# WL-FPGA.net
KiCad netlist of a schematic drawn in Altium Designer
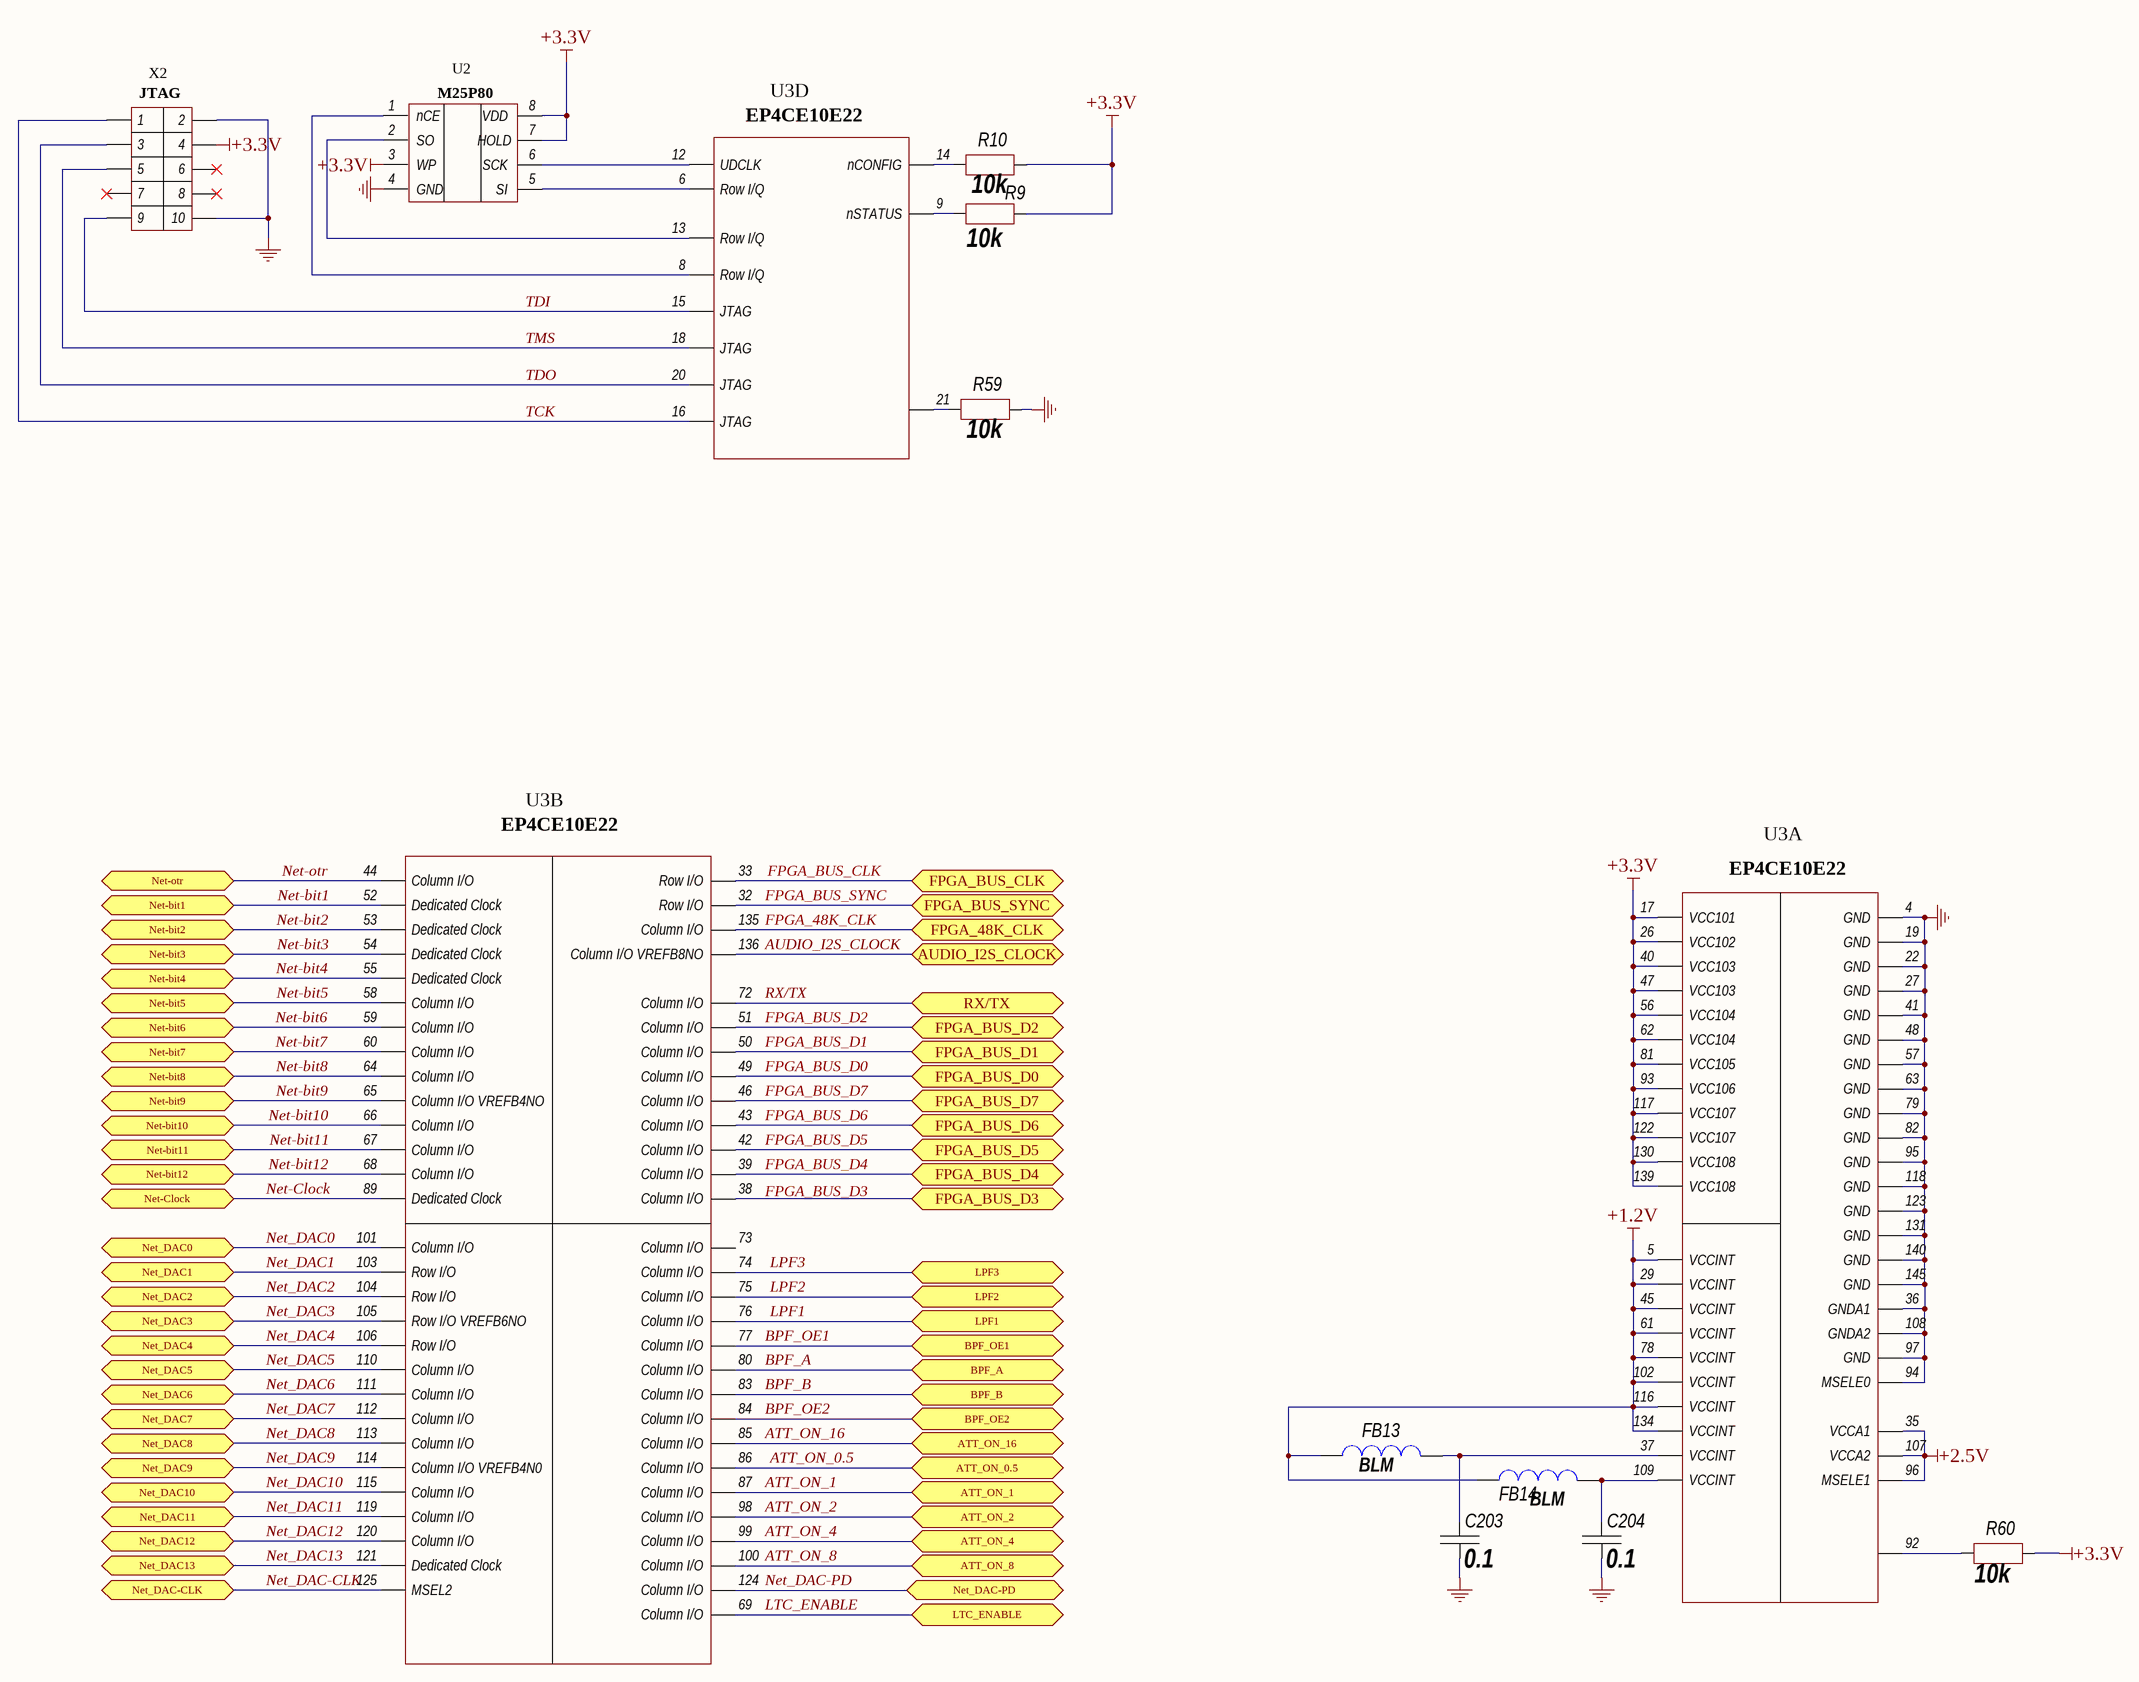
[diagram p0: WL-FPGA.SchDoc]

(export (version "E")
  (design (tool "Eeschema 10.0.6"))
  (components
    (comp (ref "C203")
      (value "0.1")
      (footprint "standard:CH0805C")
      (libsource (lib "Discrete") (part "Capacitor"))
    )
    (comp (ref "C204")
      (value "0.1")
      (footprint "standard:CH0805C")
      (libsource (lib "Discrete") (part "Capacitor"))
    )
    (comp (ref "FB13")
      (value "BLM")
      (footprint "standard:CH0805L")
      (libsource (lib "Discrete") (part "Inductor"))
    )
    (comp (ref "FB14")
      (value "BLM")
      (footprint "standard:CH0805L")
      (libsource (lib "Discrete") (part "Inductor"))
    )
    (comp (ref "R9")
      (value "10k")
      (footprint "standard:CH0805R")
      (libsource (lib "Discrete") (part "Resistor"))
    )
    (comp (ref "R10")
      (value "10k")
      (footprint "standard:CH0805R")
      (libsource (lib "Discrete") (part "Resistor"))
    )
    (comp (ref "R59")
      (value "10k")
      (footprint "standard:CH0805R")
      (libsource (lib "Discrete") (part "Resistor"))
    )
    (comp (ref "R60")
      (value "10k")
      (footprint "standard:CH0805R")
      (libsource (lib "Discrete") (part "Resistor"))
    )
    (comp (ref "U2") (value "M25P80") (footprint "8-SOIC") (libsource (lib "Digital") (part "M25P80")))
    (comp (ref "U3")
      (value "EP4CE10E22")
      (footprint "144-QFN")
      (libsource (lib "Digital") (part "EP4CE10E22C8N"))
    )
    (comp (ref "X2") (value "JTAG") (footprint "CON: PLD-10") (libsource (lib "Connectors") (part "Jtag")))
  )
  (nets
    (net (code "1") (name "+1.2V") (class "Default")
      (node (ref "FB13") (pin "2") (pinfunction "2_2") (pintype "passive"))
      (node (ref "FB14") (pin "2") (pinfunction "2_2") (pintype "passive"))
      (node (ref "U3") (pin "102") (pinfunction "VCCINT_102") (pintype "passive"))
      (node (ref "U3") (pin "116") (pinfunction "VCCINT_116") (pintype "passive"))
      (node (ref "U3") (pin "134") (pinfunction "VCCINT_134") (pintype "passive"))
      (node (ref "U3") (pin "29") (pinfunction "VCCINT_29") (pintype "passive"))
      (node (ref "U3") (pin "45") (pinfunction "VCCINT_45") (pintype "passive"))
      (node (ref "U3") (pin "5") (pinfunction "VCCINT_5") (pintype "passive"))
      (node (ref "U3") (pin "61") (pinfunction "VCCINT_61") (pintype "passive"))
      (node (ref "U3") (pin "78") (pinfunction "VCCINT_78") (pintype "passive"))
    )
    (net (code "2") (name "+2.5V") (class "Default")
      (node (ref "U3") (pin "107") (pinfunction "VCCA2_107") (pintype "passive"))
      (node (ref "U3") (pin "35") (pinfunction "VCCA1_35") (pintype "passive"))
      (node (ref "U3") (pin "96") (pinfunction "MSELE1_96") (pintype "passive"))
    )
    (net (code "3") (name "+3.3V") (class "Default")
      (node (ref "R10") (pin "1") (pinfunction "1_1") (pintype "passive"))
      (node (ref "R60") (pin "1") (pinfunction "1_1") (pintype "passive"))
      (node (ref "R9") (pin "1") (pinfunction "1_1") (pintype "passive"))
      (node (ref "U2") (pin "3") (pinfunction "WP_3") (pintype "passive"))
      (node (ref "U2") (pin "7") (pinfunction "HOLD_7") (pintype "passive"))
      (node (ref "U2") (pin "8") (pinfunction "VDD_8") (pintype "passive"))
      (node (ref "U3") (pin "117") (pinfunction "VCC107_117") (pintype "passive"))
      (node (ref "U3") (pin "122") (pinfunction "VCC107_122") (pintype "passive"))
      (node (ref "U3") (pin "130") (pinfunction "VCC108_130") (pintype "passive"))
      (node (ref "U3") (pin "139") (pinfunction "VCC108_139") (pintype "passive"))
      (node (ref "U3") (pin "17") (pinfunction "VCC101_17") (pintype "passive"))
      (node (ref "U3") (pin "26") (pinfunction "VCC102_26") (pintype "passive"))
      (node (ref "U3") (pin "40") (pinfunction "VCC103_40") (pintype "passive"))
      (node (ref "U3") (pin "47") (pinfunction "VCC103_47") (pintype "passive"))
      (node (ref "U3") (pin "56") (pinfunction "VCC104_56") (pintype "passive"))
      (node (ref "U3") (pin "62") (pinfunction "VCC104_62") (pintype "passive"))
      (node (ref "U3") (pin "81") (pinfunction "VCC105_81") (pintype "passive"))
      (node (ref "U3") (pin "93") (pinfunction "VCC106_93") (pintype "passive"))
      (node (ref "X2") (pin "4") (pinfunction "4_4") (pintype "power_in"))
    )
    (net (code "4") (name "/ATT_ON_0.5") (class "Default")
      (node (ref "U3") (pin "86") (pinfunction "Column_I/O_86") (pintype "passive"))
    )
    (net (code "5") (name "/ATT_ON_1") (class "Default")
      (node (ref "U3") (pin "87") (pinfunction "Column_I/O_87") (pintype "passive"))
    )
    (net (code "6") (name "/ATT_ON_2") (class "Default")
      (node (ref "U3") (pin "98") (pinfunction "Column_I/O_98") (pintype "passive"))
    )
    (net (code "7") (name "/ATT_ON_4") (class "Default")
      (node (ref "U3") (pin "99") (pinfunction "Column_I/O_99") (pintype "passive"))
    )
    (net (code "8") (name "/ATT_ON_8") (class "Default")
      (node (ref "U3") (pin "100") (pinfunction "Column_I/O_100") (pintype "passive"))
    )
    (net (code "9") (name "/ATT_ON_16") (class "Default")
      (node (ref "U3") (pin "85") (pinfunction "Column_I/O_85") (pintype "passive"))
    )
    (net (code "10") (name "/AUDIO_I2S_CLOCK") (class "Default")
      (node (ref "U3") (pin "136") (pinfunction "Column_I/O_VREFB8NO_136") (pintype "passive"))
    )
    (net (code "11") (name "/BPF_A") (class "Default")
      (node (ref "U3") (pin "80") (pinfunction "Column_I/O_80") (pintype "passive"))
    )
    (net (code "12") (name "/BPF_B") (class "Default")
      (node (ref "U3") (pin "83") (pinfunction "Column_I/O_83") (pintype "passive"))
    )
    (net (code "13") (name "/BPF_OE1") (class "Default")
      (node (ref "U3") (pin "77") (pinfunction "Column_I/O_77") (pintype "passive"))
    )
    (net (code "14") (name "/BPF_OE2") (class "Default")
      (node (ref "U3") (pin "84") (pinfunction "Column_I/O_84") (pintype "passive"))
    )
    (net (code "15") (name "/FPGA_48K_CLK") (class "Default")
      (node (ref "U3") (pin "135") (pinfunction "Column_I/O_135") (pintype "passive"))
    )
    (net (code "16") (name "/FPGA_BUS_CLK") (class "Default")
      (node (ref "U3") (pin "33") (pinfunction "Row_I/O_33") (pintype "passive"))
    )
    (net (code "17") (name "/FPGA_BUS_D0") (class "Default")
      (node (ref "U3") (pin "49") (pinfunction "Column_I/O_49") (pintype "passive"))
    )
    (net (code "18") (name "/FPGA_BUS_D1") (class "Default")
      (node (ref "U3") (pin "50") (pinfunction "Column_I/O_50") (pintype "passive"))
    )
    (net (code "19") (name "/FPGA_BUS_D2") (class "Default")
      (node (ref "U3") (pin "51") (pinfunction "Column_I/O_51") (pintype "passive"))
    )
    (net (code "20") (name "/FPGA_BUS_D3") (class "Default")
      (node (ref "U3") (pin "38") (pinfunction "Column_I/O_38") (pintype "passive"))
    )
    (net (code "21") (name "/FPGA_BUS_D4") (class "Default")
      (node (ref "U3") (pin "39") (pinfunction "Column_I/O_39") (pintype "passive"))
    )
    (net (code "22") (name "/FPGA_BUS_D5") (class "Default")
      (node (ref "U3") (pin "42") (pinfunction "Column_I/O_42") (pintype "passive"))
    )
    (net (code "23") (name "/FPGA_BUS_D6") (class "Default")
      (node (ref "U3") (pin "43") (pinfunction "Column_I/O_43") (pintype "passive"))
    )
    (net (code "24") (name "/FPGA_BUS_D7") (class "Default")
      (node (ref "U3") (pin "46") (pinfunction "Column_I/O_46") (pintype "passive"))
    )
    (net (code "25") (name "/FPGA_BUS_SYNC") (class "Default")
      (node (ref "U3") (pin "32") (pinfunction "Row_I/O_32") (pintype "passive"))
    )
    (net (code "26") (name "/LPF1") (class "Default")
      (node (ref "U3") (pin "76") (pinfunction "Column_I/O_76") (pintype "passive"))
    )
    (net (code "27") (name "/LPF2") (class "Default")
      (node (ref "U3") (pin "75") (pinfunction "Column_I/O_75") (pintype "passive"))
    )
    (net (code "28") (name "/LPF3") (class "Default")
      (node (ref "U3") (pin "74") (pinfunction "Column_I/O_74") (pintype "passive"))
    )
    (net (code "29") (name "/LTC_ENABLE") (class "Default")
      (node (ref "U3") (pin "69") (pinfunction "Column_I/O_69") (pintype "passive"))
    )
    (net (code "30") (name "/Net-Clock") (class "Default")
      (node (ref "U3") (pin "89") (pinfunction "Dedicated_Clock_89") (pintype "passive"))
    )
    (net (code "31") (name "/Net-bit1") (class "Default")
      (node (ref "U3") (pin "52") (pinfunction "Dedicated_Clock_52") (pintype "passive"))
    )
    (net (code "32") (name "/Net-bit2") (class "Default")
      (node (ref "U3") (pin "53") (pinfunction "Dedicated_Clock_53") (pintype "passive"))
    )
    (net (code "33") (name "/Net-bit3") (class "Default")
      (node (ref "U3") (pin "54") (pinfunction "Dedicated_Clock_54") (pintype "passive"))
    )
    (net (code "34") (name "/Net-bit4") (class "Default")
      (node (ref "U3") (pin "55") (pinfunction "Dedicated_Clock_55") (pintype "passive"))
    )
    (net (code "35") (name "/Net-bit5") (class "Default")
      (node (ref "U3") (pin "58") (pinfunction "Column_I/O_58") (pintype "passive"))
    )
    (net (code "36") (name "/Net-bit6") (class "Default")
      (node (ref "U3") (pin "59") (pinfunction "Column_I/O_59") (pintype "passive"))
    )
    (net (code "37") (name "/Net-bit7") (class "Default")
      (node (ref "U3") (pin "60") (pinfunction "Column_I/O_60") (pintype "passive"))
    )
    (net (code "38") (name "/Net-bit8") (class "Default")
      (node (ref "U3") (pin "64") (pinfunction "Column_I/O_64") (pintype "passive"))
    )
    (net (code "39") (name "/Net-bit9") (class "Default")
      (node (ref "U3") (pin "65") (pinfunction "Column_I/O_VREFB4NO_65") (pintype "passive"))
    )
    (net (code "40") (name "/Net-bit10") (class "Default")
      (node (ref "U3") (pin "66") (pinfunction "Column_I/O_66") (pintype "passive"))
    )
    (net (code "41") (name "/Net-bit11") (class "Default")
      (node (ref "U3") (pin "67") (pinfunction "Column_I/O_67") (pintype "passive"))
    )
    (net (code "42") (name "/Net-bit12") (class "Default")
      (node (ref "U3") (pin "68") (pinfunction "Column_I/O_68") (pintype "passive"))
    )
    (net (code "43") (name "/Net-otr") (class "Default")
      (node (ref "U3") (pin "44") (pinfunction "Column_I/O_44") (pintype "passive"))
    )
    (net (code "44") (name "/Net_DAC-CLK") (class "Default")
      (node (ref "U3") (pin "125") (pinfunction "MSEL2_125") (pintype "passive"))
    )
    (net (code "45") (name "/Net_DAC-PD") (class "Default")
      (node (ref "U3") (pin "124") (pinfunction "Column_I/O_124") (pintype "passive"))
    )
    (net (code "46") (name "/Net_DAC0") (class "Default")
      (node (ref "U3") (pin "101") (pinfunction "Column_I/O_101") (pintype "passive"))
    )
    (net (code "47") (name "/Net_DAC1") (class "Default")
      (node (ref "U3") (pin "103") (pinfunction "Row_I/O_103") (pintype "passive"))
    )
    (net (code "48") (name "/Net_DAC2") (class "Default")
      (node (ref "U3") (pin "104") (pinfunction "Row_I/O_104") (pintype "passive"))
    )
    (net (code "49") (name "/Net_DAC3") (class "Default")
      (node (ref "U3") (pin "105") (pinfunction "Row_I/O_VREFB6NO_105") (pintype "passive"))
    )
    (net (code "50") (name "/Net_DAC4") (class "Default")
      (node (ref "U3") (pin "106") (pinfunction "Row_I/O_106") (pintype "passive"))
    )
    (net (code "51") (name "/Net_DAC5") (class "Default")
      (node (ref "U3") (pin "110") (pinfunction "Column_I/O_110") (pintype "passive"))
    )
    (net (code "52") (name "/Net_DAC6") (class "Default")
      (node (ref "U3") (pin "111") (pinfunction "Column_I/O_111") (pintype "passive"))
    )
    (net (code "53") (name "/Net_DAC7") (class "Default")
      (node (ref "U3") (pin "112") (pinfunction "Column_I/O_112") (pintype "passive"))
    )
    (net (code "54") (name "/Net_DAC8") (class "Default")
      (node (ref "U3") (pin "113") (pinfunction "Column_I/O_113") (pintype "passive"))
    )
    (net (code "55") (name "/Net_DAC9") (class "Default")
      (node (ref "U3") (pin "114") (pinfunction "Column_I/O_VREFB4N0_114") (pintype "passive"))
    )
    (net (code "56") (name "/Net_DAC10") (class "Default")
      (node (ref "U3") (pin "115") (pinfunction "Column_I/O_115") (pintype "passive"))
    )
    (net (code "57") (name "/Net_DAC11") (class "Default")
      (node (ref "U3") (pin "119") (pinfunction "Column_I/O_119") (pintype "passive"))
    )
    (net (code "58") (name "/Net_DAC12") (class "Default")
      (node (ref "U3") (pin "120") (pinfunction "Column_I/O_120") (pintype "passive"))
    )
    (net (code "59") (name "/Net_DAC13") (class "Default")
      (node (ref "U3") (pin "121") (pinfunction "Dedicated_Clock_121") (pintype "passive"))
    )
    (net (code "60") (name "/RX{slash}TX") (class "Default")
      (node (ref "U3") (pin "72") (pinfunction "Column_I/O_72") (pintype "passive"))
    )
    (net (code "61") (name "/TCK") (class "Default")
      (node (ref "U3") (pin "16") (pinfunction "JTAG_16") (pintype "passive"))
      (node (ref "X2") (pin "1") (pinfunction "1_1") (pintype "passive"))
    )
    (net (code "62") (name "/TDI") (class "Default")
      (node (ref "U3") (pin "15") (pinfunction "JTAG_15") (pintype "power_in"))
      (node (ref "X2") (pin "9") (pinfunction "9_9") (pintype "power_in"))
    )
    (net (code "63") (name "/TDO") (class "Default")
      (node (ref "U3") (pin "20") (pinfunction "JTAG_20") (pintype "passive"))
      (node (ref "X2") (pin "3") (pinfunction "3_3") (pintype "passive"))
    )
    (net (code "64") (name "/TMS") (class "Default")
      (node (ref "U3") (pin "18") (pinfunction "JTAG_18") (pintype "passive"))
      (node (ref "X2") (pin "5") (pinfunction "5_5") (pintype "power_in"))
    )
    (net (code "65") (name "GND") (class "Default")
      (node (ref "C203") (pin "1") (pinfunction "1_1") (pintype "power_in"))
      (node (ref "C204") (pin "1") (pinfunction "1_1") (pintype "power_in"))
      (node (ref "R59") (pin "1") (pinfunction "1_1") (pintype "passive"))
      (node (ref "U2") (pin "4") (pinfunction "GND_4") (pintype "passive"))
      (node (ref "U3") (pin "108") (pinfunction "GNDA2_108") (pintype "passive"))
      (node (ref "U3") (pin "118") (pinfunction "GND_118") (pintype "passive"))
      (node (ref "U3") (pin "123") (pinfunction "GND_123") (pintype "passive"))
      (node (ref "U3") (pin "131") (pinfunction "GND_131") (pintype "passive"))
      (node (ref "U3") (pin "140") (pinfunction "GND_140") (pintype "passive"))
      (node (ref "U3") (pin "145") (pinfunction "GND_145") (pintype "passive"))
      (node (ref "U3") (pin "19") (pinfunction "GND_19") (pintype "passive"))
      (node (ref "U3") (pin "22") (pinfunction "GND_22") (pintype "passive"))
      (node (ref "U3") (pin "27") (pinfunction "GND_27") (pintype "passive"))
      (node (ref "U3") (pin "36") (pinfunction "GNDA1_36") (pintype "passive"))
      (node (ref "U3") (pin "4") (pinfunction "GND_4") (pintype "passive"))
      (node (ref "U3") (pin "41") (pinfunction "GND_41") (pintype "passive"))
      (node (ref "U3") (pin "48") (pinfunction "GND_48") (pintype "passive"))
      (node (ref "U3") (pin "57") (pinfunction "GND_57") (pintype "passive"))
      (node (ref "U3") (pin "63") (pinfunction "GND_63") (pintype "passive"))
      (node (ref "U3") (pin "79") (pinfunction "GND_79") (pintype "passive"))
      (node (ref "U3") (pin "82") (pinfunction "GND_82") (pintype "passive"))
      (node (ref "U3") (pin "94") (pinfunction "MSELE0_94") (pintype "passive"))
      (node (ref "U3") (pin "95") (pinfunction "GND_95") (pintype "passive"))
      (node (ref "U3") (pin "97") (pinfunction "GND_97") (pintype "passive"))
      (node (ref "X2") (pin "10") (pinfunction "10_10") (pintype "power_in"))
      (node (ref "X2") (pin "2") (pinfunction "2_2") (pintype "power_in"))
    )
    (net (code "66") (name "Net-(C203-Pad2)") (class "Default")
      (node (ref "C203") (pin "2") (pinfunction "2_2") (pintype "power_in"))
      (node (ref "FB13") (pin "1") (pinfunction "1_1") (pintype "passive"))
      (node (ref "U3") (pin "37") (pinfunction "VCCINT_37") (pintype "passive"))
    )
    (net (code "67") (name "Net-(C204-Pad2)") (class "Default")
      (node (ref "C204") (pin "2") (pinfunction "2_2") (pintype "power_in"))
      (node (ref "FB14") (pin "1") (pinfunction "1_1") (pintype "passive"))
      (node (ref "U3") (pin "109") (pinfunction "VCCINT_109") (pintype "passive"))
    )
    (net (code "68") (name "Net-(R60-Pad2)") (class "Default")
      (node (ref "R60") (pin "2") (pinfunction "2_2") (pintype "passive"))
      (node (ref "U3") (pin "92") (pintype "passive"))
    )
    (net (code "69") (name "Net-(U2-SCK)") (class "Default")
      (node (ref "U2") (pin "6") (pinfunction "SCK_6") (pintype "passive"))
      (node (ref "U3") (pin "12") (pinfunction "UDCLK_12") (pintype "passive"))
    )
    (net (code "70") (name "Net-(U2-SI)") (class "Default")
      (node (ref "U2") (pin "5") (pinfunction "SI_5") (pintype "passive"))
      (node (ref "U3") (pin "6") (pinfunction "Row_I/Q_6") (pintype "passive"))
    )
    (net (code "71") (name "Net-(U2-SO)") (class "Default")
      (node (ref "U2") (pin "2") (pinfunction "SO_2") (pintype "passive"))
      (node (ref "U3") (pin "13") (pinfunction "Row_I/Q_13") (pintype "passive"))
    )
    (net (code "72") (name "Net-(U2-nCE)") (class "Default")
      (node (ref "U2") (pin "1") (pinfunction "nCE_1") (pintype "passive"))
      (node (ref "U3") (pin "8") (pinfunction "Row_I/Q_8") (pintype "passive"))
    )
    (net (code "73") (name "Net-(U3D-nCE)") (class "Default")
      (node (ref "R59") (pin "2") (pinfunction "2_2") (pintype "passive"))
      (node (ref "U3") (pin "21") (pinfunction "nCE_21") (pintype "passive"))
    )
    (net (code "74") (name "Net-(U3D-nCONFIG)") (class "Default")
      (node (ref "R10") (pin "2") (pinfunction "2_2") (pintype "passive"))
      (node (ref "U3") (pin "14") (pinfunction "nCONFIG_14") (pintype "passive"))
    )
    (net (code "75") (name "Net-(U3D-nSTATUS)") (class "Default")
      (node (ref "R9") (pin "2") (pinfunction "2_2") (pintype "passive"))
      (node (ref "U3") (pin "9") (pinfunction "nSTATUS_9") (pintype "passive"))
    )
    (net (code "76") (name "unconnected-(U3B-Column_I{slash}O-Pad73)") (class "Default")
      (node (ref "U3") (pin "73") (pinfunction "Column_I/O_73") (pintype "passive"))
    )
    (net (code "77") (name "unconnected-(X2-Pad6)") (class "Default")
      (node (ref "X2") (pin "6") (pinfunction "6_6") (pintype "power_in+no_connect"))
    )
    (net (code "78") (name "unconnected-(X2-Pad7)") (class "Default")
      (node (ref "X2") (pin "7") (pinfunction "7_7") (pintype "power_in+no_connect"))
    )
    (net (code "79") (name "unconnected-(X2-Pad8)") (class "Default")
      (node (ref "X2") (pin "8") (pinfunction "8_8") (pintype "power_in+no_connect"))
    )
  )
)
